# HDMI.net
KiCad netlist of a schematic drawn in Altium Designer
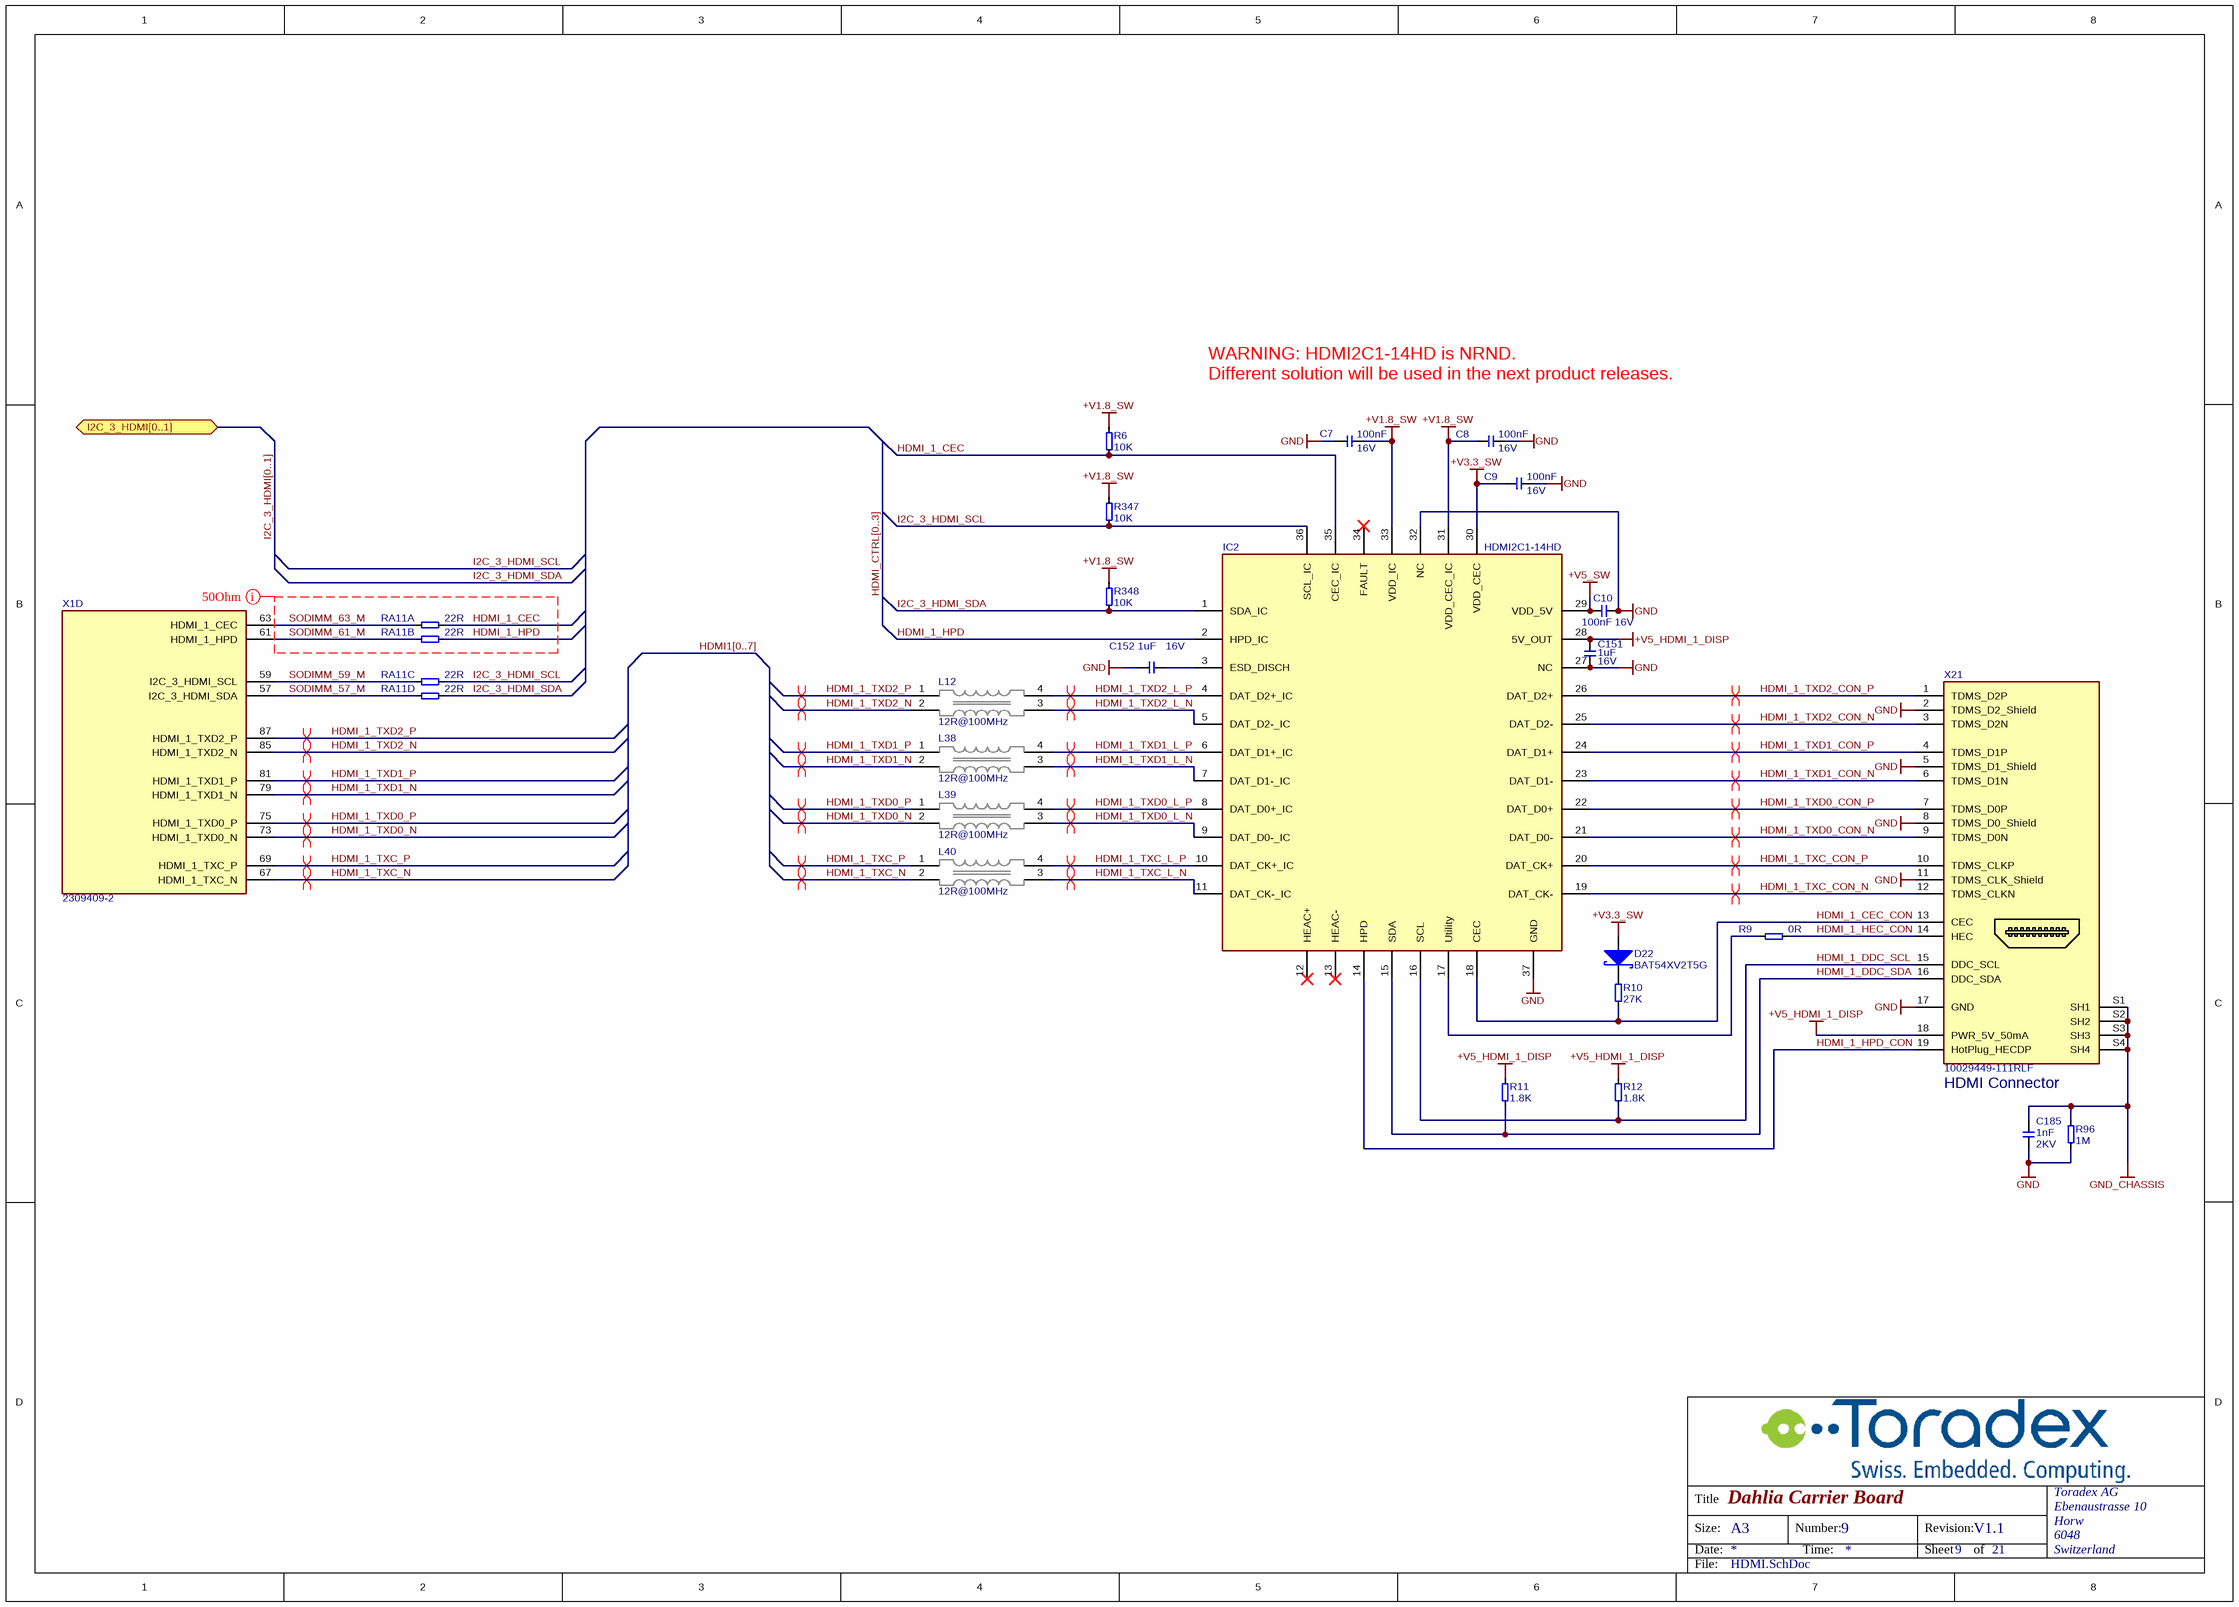
[diagram p0: HDMI.SchDoc]

(export (version "E")
  (design (tool "Eeschema 10.0.6"))
  (components
    (comp (ref "C7")
      (value "100nF")
      (footprint "CAPC1005X60N")
      (description "Capacitor Ceramic X7R 100nF 16V 10% 0402")
      (fields (field (name "TOLERANCE") "10%") (field (name "RATING") "16V"))
      (libsource (lib "Dahlia Carrier Board") (part "C-X7R-100nF-16V-10%-0402"))
    )
    (comp (ref "C8")
      (value "100nF")
      (footprint "CAPC1005X60N")
      (description "Capacitor Ceramic X7R 100nF 16V 10% 0402")
      (fields (field (name "TOLERANCE") "10%") (field (name "RATING") "16V"))
      (libsource (lib "Dahlia Carrier Board") (part "C-X7R-100nF-16V-10%-0402"))
    )
    (comp (ref "C9")
      (value "100nF")
      (footprint "CAPC1005X60N")
      (description "Capacitor Ceramic X7R 100nF 16V 10% 0402")
      (fields (field (name "TOLERANCE") "10%") (field (name "RATING") "16V"))
      (libsource (lib "Dahlia Carrier Board") (part "C-X7R-100nF-16V-10%-0402"))
    )
    (comp (ref "C10")
      (value "100nF")
      (footprint "CAPC1005X60N")
      (description "Capacitor Ceramic X7R 100nF 16V 10% 0402")
      (fields (field (name "TOLERANCE") "10%") (field (name "RATING") "16V"))
      (libsource (lib "Dahlia Carrier Board") (part "C-X7R-100nF-16V-10%-0402"))
    )
    (comp (ref "C151")
      (value "1uF")
      (footprint "CAPC1005X60N")
      (description "Capacitor Ceramic X5R 1uF 16V 20% 0402")
      (fields (field (name "TOLERANCE") "20%") (field (name "RATING") "16V"))
      (libsource (lib "Dahlia Carrier Board") (part "C-X5R-1uF-16V-20%-0402"))
    )
    (comp (ref "C152")
      (value "1uF")
      (footprint "CAPC1005X60N")
      (description "Capacitor Ceramic X5R 1uF 16V 20% 0402")
      (fields (field (name "TOLERANCE") "20%") (field (name "RATING") "16V"))
      (libsource (lib "Dahlia Carrier Board") (part "C-X5R-1uF-16V-20%-0402"))
    )
    (comp (ref "C185")
      (value "1nF")
      (footprint "T_CAPC1206X180N")
      (description "Capacitor Ceramic X7R 1nF 2KV 10% 1206")
      (fields (field (name "TOLERANCE") "10%") (field (name "RATING") "2KV"))
      (libsource (lib "Dahlia Carrier Board") (part "C-X7R-1nF-2KV-10%-1206"))
    )
    (comp (ref "D22")
      (value "BAT54XV2T5G")
      (footprint "SOD-523")
      (description "Schottky Barrier Rectifier")
      (fields (field (name "MANUFACTURER PART NO.") "BAT54XV2T5G"))
      (libsource (lib "Dahlia Carrier Board") (part "D-BAT54-SOD523"))
    )
    (comp (ref "IC2")
      (value "HDMI2C1-14HD")
      (footprint "QFN50P350X650X95_HS-37N")
      (description "ESD protection and signal conditioning for HDMI™ 2.0 source interface")
      (fields (field (name "MANUFACTURER PART NO.") "HDMI2C1-14HD"))
      (libsource (lib "Dahlia Carrier Board") (part "IC-ST-HDMI2C1-14HD"))
    )
    (comp (ref "L12")
      (value "12R@100MHz")
      (footprint "T_Panasonic_EXC14CH120U")
      (description "Common Mode Choke High Speed 12R 100mA")
      (fields (field (name "TOLERANCE") "25%") (field (name "MANUFACTURER PART NO.") "EXC14CH120U"))
      (libsource (lib "Dahlia Carrier Board") (part "L-Panasonic-EXC14CH120U-12R@100MHz-1000mA-25%"))
    )
    (comp (ref "L38")
      (value "12R@100MHz")
      (footprint "T_Panasonic_EXC14CH120U")
      (description "Common Mode Choke High Speed 12R 100mA")
      (fields (field (name "TOLERANCE") "25%") (field (name "MANUFACTURER PART NO.") "EXC14CH120U"))
      (libsource (lib "Dahlia Carrier Board") (part "L-Panasonic-EXC14CH120U-12R@100MHz-1000mA-25%"))
    )
    (comp (ref "L39")
      (value "12R@100MHz")
      (footprint "T_Panasonic_EXC14CH120U")
      (description "Common Mode Choke High Speed 12R 100mA")
      (fields (field (name "TOLERANCE") "25%") (field (name "MANUFACTURER PART NO.") "EXC14CH120U"))
      (libsource (lib "Dahlia Carrier Board") (part "L-Panasonic-EXC14CH120U-12R@100MHz-1000mA-25%"))
    )
    (comp (ref "L40")
      (value "12R@100MHz")
      (footprint "T_Panasonic_EXC14CH120U")
      (description "Common Mode Choke High Speed 12R 100mA")
      (fields (field (name "TOLERANCE") "25%") (field (name "MANUFACTURER PART NO.") "EXC14CH120U"))
      (libsource (lib "Dahlia Carrier Board") (part "L-Panasonic-EXC14CH120U-12R@100MHz-1000mA-25%"))
    )
    (comp (ref "R6")
      (value "10K")
      (footprint "RESC1005X40N")
      (description "Resistor 10 Kohm 63mW 5% 0402")
      (fields (field (name "TOLERANCE") "5%"))
      (libsource (lib "Dahlia Carrier Board") (part "R-10K-63mW-5%-0402"))
    )
    (comp (ref "R9")
      (value "0R")
      (footprint "T_RESC0603X30N")
      (description "Resistor 0 ohm 63mW 1% 0603")
      (fields (field (name "TOLERANCE") "1%"))
      (libsource (lib "Dahlia Carrier Board") (part "R-0R-63mW-1%-0603"))
    )
    (comp (ref "R10")
      (value "27K")
      (footprint "RESC1005X40N")
      (description "Resistor 27 Kohm 63mW 5% 0402")
      (fields (field (name "TOLERANCE") "5%"))
      (libsource (lib "Dahlia Carrier Board") (part "R-27K-63mW-5%-0402"))
    )
    (comp (ref "R11")
      (value "1.8K")
      (footprint "RESC1005X40N")
      (description "Resistor 1.8 Kohm 63mW 5% 0402")
      (fields (field (name "TOLERANCE") "5%"))
      (libsource (lib "Dahlia Carrier Board") (part "R-1.8K-63mW-5%-0402"))
    )
    (comp (ref "R12")
      (value "1.8K")
      (footprint "RESC1005X40N")
      (description "Resistor 1.8 Kohm 63mW 5% 0402")
      (fields (field (name "TOLERANCE") "5%"))
      (libsource (lib "Dahlia Carrier Board") (part "R-1.8K-63mW-5%-0402"))
    )
    (comp (ref "R96")
      (value "1M")
      (footprint "RESC3216X75N")
      (description "Resistor 1 Mohm 250mW 5% 1206")
      (fields (field (name "TOLERANCE") "5%"))
      (libsource (lib "Dahlia Carrier Board") (part "R-1M-250mW-5%-1206"))
    )
    (comp (ref "R347")
      (value "10K")
      (footprint "RESC1005X40N")
      (description "Resistor 10 Kohm 63mW 5% 0402")
      (fields (field (name "TOLERANCE") "5%"))
      (libsource (lib "Dahlia Carrier Board") (part "R-10K-63mW-5%-0402"))
    )
    (comp (ref "R348")
      (value "10K")
      (footprint "RESC1005X40N")
      (description "Resistor 10 Kohm 63mW 5% 0402")
      (fields (field (name "TOLERANCE") "5%"))
      (libsource (lib "Dahlia Carrier Board") (part "R-10K-63mW-5%-0402"))
    )
    (comp (ref "RA11")
      (value "22R")
      (footprint "T_Resistor_Array_X4")
      (description "Resistor Array 22 R 63mW 5% 1206")
      (fields (field (name "TOLERANCE") "5%"))
      (libsource (lib "Dahlia Carrier Board") (part "RA-22R-63mW-5%-1206-div"))
    )
    (comp (ref "X1")
      (value "2309409-2")
      (footprint "CON-TE-2309409-2-SOLDERABLE-STANDOFFS")
      (description "DDR4 SODIMM Socket, 260 pins, 5.2mm(H), 0.5mm Pitch")
      (libsource (lib "Dahlia Carrier Board") (part "CON-TE-2309409-2"))
    )
    (comp (ref "X21")
      (value "10029449-111RLF")
      (footprint "T_FCI_10029449-111RLF")
      (description "HDMI Connector Right Angle Vertical THT")
      (fields (field (name "MANUFACTURER PART NO.") "10029449-111RLF"))
      (libsource (lib "Dahlia Carrier Board") (part "CON-FCI-10029449-111RLF"))
    )
  )
  (nets
    (net (code "15") (name "+V1.8_SW") (class "Default")
      (node (ref "C7") (pin "2") (pinfunction "2_2") (pintype "passive"))
      (node (ref "C8") (pin "1") (pinfunction "1_1") (pintype "passive"))
      (node (ref "IC2") (pin "31") (pinfunction "VDD_CEC_IC_31") (pintype "passive"))
      (node (ref "IC2") (pin "33") (pinfunction "VDD_IC_33") (pintype "power_in"))
      (node (ref "R347") (pin "1") (pinfunction "1_1") (pintype "passive"))
      (node (ref "R348") (pin "1") (pinfunction "1_1") (pintype "passive"))
      (node (ref "R6") (pin "2") (pinfunction "2_2") (pintype "passive"))
    )
    (net (code "16") (name "+V3.3_SW") (class "Default")
      (node (ref "C9") (pin "2") (pinfunction "2_2") (pintype "passive"))
      (node (ref "D22") (pin "A") (pinfunction "A_A") (pintype "passive"))
      (node (ref "IC2") (pin "30") (pinfunction "VDD_CEC_30") (pintype "passive"))
    )
    (net (code "17") (name "+V5_HDMI_1_DISP") (class "Default")
      (node (ref "C151") (pin "2") (pinfunction "2_2") (pintype "passive"))
      (node (ref "IC2") (pin "28") (pinfunction "5V_OUT_28") (pintype "power_in"))
      (node (ref "R11") (pin "2") (pinfunction "2_2") (pintype "passive"))
      (node (ref "R12") (pin "2") (pinfunction "2_2") (pintype "passive"))
      (node (ref "X21") (pin "18") (pinfunction "PWR_5V_50mA_18") (pintype "passive"))
    )
    (net (code "18") (name "+V5_SW") (class "Default")
      (node (ref "C10") (pin "2") (pinfunction "2_2") (pintype "passive"))
      (node (ref "IC2") (pin "29") (pinfunction "VDD_5V_29") (pintype "power_in"))
    )
    (net (code "20") (name "/HDMI_1_CEC") (class "Default")
      (node (ref "IC2") (pin "35") (pinfunction "CEC_IC_35") (pintype "passive"))
      (node (ref "R6") (pin "1") (pinfunction "1_1") (pintype "passive"))
      (node (ref "RA11") (pin "5") (pinfunction "5_5") (pintype "passive"))
    )
    (net (code "21") (name "/HDMI_1_CEC_CON") (class "Default")
      (node (ref "IC2") (pin "18") (pinfunction "CEC_18") (pintype "passive"))
      (node (ref "R10") (pin "1") (pinfunction "1_1") (pintype "passive"))
      (node (ref "X21") (pin "13") (pinfunction "CEC_13") (pintype "passive"))
    )
    (net (code "22") (name "/HDMI_1_DDC_SCL") (class "Default")
      (node (ref "IC2") (pin "16") (pinfunction "SCL_16") (pintype "passive"))
      (node (ref "R12") (pin "1") (pinfunction "1_1") (pintype "passive"))
      (node (ref "X21") (pin "15") (pinfunction "DDC_SCL_15") (pintype "passive"))
    )
    (net (code "23") (name "/HDMI_1_DDC_SDA") (class "Default")
      (node (ref "IC2") (pin "15") (pinfunction "SDA_15") (pintype "passive"))
      (node (ref "R11") (pin "1") (pinfunction "1_1") (pintype "passive"))
      (node (ref "X21") (pin "16") (pinfunction "DDC_SDA_16") (pintype "passive"))
    )
    (net (code "24") (name "/HDMI_1_HEC_CON") (class "Default")
      (node (ref "R9") (pin "2") (pinfunction "2_2") (pintype "passive"))
      (node (ref "X21") (pin "14") (pinfunction "HEC_14") (pintype "passive"))
    )
    (net (code "25") (name "/HDMI_1_HPD") (class "Default")
      (node (ref "IC2") (pin "2") (pinfunction "HPD_IC_2") (pintype "passive"))
      (node (ref "RA11") (pin "6") (pinfunction "6_6") (pintype "passive"))
    )
    (net (code "26") (name "/HDMI_1_HPD_CON") (class "Default")
      (node (ref "IC2") (pin "14") (pinfunction "HPD_14") (pintype "passive"))
      (node (ref "X21") (pin "19") (pinfunction "HotPlug_HECDP_19") (pintype "passive"))
    )
    (net (code "27") (name "/HDMI_1_TXC_CON_N") (class "Default")
      (node (ref "IC2") (pin "19") (pinfunction "DAT_CK-_19") (pintype "passive"))
      (node (ref "X21") (pin "12") (pinfunction "TDMS_CLKN_12") (pintype "passive"))
    )
    (net (code "28") (name "/HDMI_1_TXC_CON_P") (class "Default")
      (node (ref "IC2") (pin "20") (pinfunction "DAT_CK+_20") (pintype "passive"))
      (node (ref "X21") (pin "10") (pinfunction "TDMS_CLKP_10") (pintype "passive"))
    )
    (net (code "29") (name "/HDMI_1_TXC_L_N") (class "Default")
      (node (ref "IC2") (pin "11") (pinfunction "DAT_CK-_IC_11") (pintype "passive"))
      (node (ref "L40") (pin "3") (pinfunction "3_3") (pintype "passive"))
    )
    (net (code "30") (name "/HDMI_1_TXC_L_P") (class "Default")
      (node (ref "IC2") (pin "10") (pinfunction "DAT_CK+_IC_10") (pintype "passive"))
      (node (ref "L40") (pin "4") (pinfunction "4_4") (pintype "passive"))
    )
    (net (code "31") (name "/HDMI_1_TXC_N") (class "Default")
      (node (ref "L40") (pin "2") (pinfunction "2_2") (pintype "passive"))
      (node (ref "X1") (pin "67") (pinfunction "HDMI_1_TXC_N_67") (pintype "passive"))
    )
    (net (code "32") (name "/HDMI_1_TXC_P") (class "Default")
      (node (ref "L40") (pin "1") (pinfunction "1_1") (pintype "passive"))
      (node (ref "X1") (pin "69") (pinfunction "HDMI_1_TXC_P_69") (pintype "passive"))
    )
    (net (code "33") (name "/HDMI_1_TXD0_CON_N") (class "Default")
      (node (ref "IC2") (pin "21") (pinfunction "DAT_D0-_21") (pintype "passive"))
      (node (ref "X21") (pin "9") (pinfunction "TDMS_D0N_9") (pintype "passive"))
    )
    (net (code "34") (name "/HDMI_1_TXD0_CON_P") (class "Default")
      (node (ref "IC2") (pin "22") (pinfunction "DAT_D0+_22") (pintype "passive"))
      (node (ref "X21") (pin "7") (pinfunction "TDMS_D0P_7") (pintype "passive"))
    )
    (net (code "35") (name "/HDMI_1_TXD0_L_N") (class "Default")
      (node (ref "IC2") (pin "9") (pinfunction "DAT_D0-_IC_9") (pintype "passive"))
      (node (ref "L39") (pin "3") (pinfunction "3_3") (pintype "passive"))
    )
    (net (code "36") (name "/HDMI_1_TXD0_L_P") (class "Default")
      (node (ref "IC2") (pin "8") (pinfunction "DAT_D0+_IC_8") (pintype "passive"))
      (node (ref "L39") (pin "4") (pinfunction "4_4") (pintype "passive"))
    )
    (net (code "37") (name "/HDMI_1_TXD0_N") (class "Default")
      (node (ref "L39") (pin "2") (pinfunction "2_2") (pintype "passive"))
      (node (ref "X1") (pin "73") (pinfunction "HDMI_1_TXD0_N_73") (pintype "passive"))
    )
    (net (code "38") (name "/HDMI_1_TXD0_P") (class "Default")
      (node (ref "L39") (pin "1") (pinfunction "1_1") (pintype "passive"))
      (node (ref "X1") (pin "75") (pinfunction "HDMI_1_TXD0_P_75") (pintype "passive"))
    )
    (net (code "39") (name "/HDMI_1_TXD1_CON_N") (class "Default")
      (node (ref "IC2") (pin "23") (pinfunction "DAT_D1-_23") (pintype "passive"))
      (node (ref "X21") (pin "6") (pinfunction "TDMS_D1N_6") (pintype "passive"))
    )
    (net (code "40") (name "/HDMI_1_TXD1_CON_P") (class "Default")
      (node (ref "IC2") (pin "24") (pinfunction "DAT_D1+_24") (pintype "passive"))
      (node (ref "X21") (pin "4") (pinfunction "TDMS_D1P_4") (pintype "passive"))
    )
    (net (code "41") (name "/HDMI_1_TXD1_L_N") (class "Default")
      (node (ref "IC2") (pin "7") (pinfunction "DAT_D1-_IC_7") (pintype "passive"))
      (node (ref "L38") (pin "3") (pinfunction "3_3") (pintype "passive"))
    )
    (net (code "42") (name "/HDMI_1_TXD1_L_P") (class "Default")
      (node (ref "IC2") (pin "6") (pinfunction "DAT_D1+_IC_6") (pintype "passive"))
      (node (ref "L38") (pin "4") (pinfunction "4_4") (pintype "passive"))
    )
    (net (code "43") (name "/HDMI_1_TXD1_N") (class "Default")
      (node (ref "L38") (pin "2") (pinfunction "2_2") (pintype "passive"))
      (node (ref "X1") (pin "79") (pinfunction "HDMI_1_TXD1_N_79") (pintype "passive"))
    )
    (net (code "44") (name "/HDMI_1_TXD1_P") (class "Default")
      (node (ref "L38") (pin "1") (pinfunction "1_1") (pintype "passive"))
      (node (ref "X1") (pin "81") (pinfunction "HDMI_1_TXD1_P_81") (pintype "passive"))
    )
    (net (code "45") (name "/HDMI_1_TXD2_CON_N") (class "Default")
      (node (ref "IC2") (pin "25") (pinfunction "DAT_D2-_25") (pintype "passive"))
      (node (ref "X21") (pin "3") (pinfunction "TDMS_D2N_3") (pintype "passive"))
    )
    (net (code "46") (name "/HDMI_1_TXD2_CON_P") (class "Default")
      (node (ref "IC2") (pin "26") (pinfunction "DAT_D2+_26") (pintype "passive"))
      (node (ref "X21") (pin "1") (pinfunction "TDMS_D2P_1") (pintype "passive"))
    )
    (net (code "47") (name "/HDMI_1_TXD2_L_N") (class "Default")
      (node (ref "IC2") (pin "5") (pinfunction "DAT_D2-_IC_5") (pintype "passive"))
      (node (ref "L12") (pin "3") (pinfunction "3_3") (pintype "passive"))
    )
    (net (code "48") (name "/HDMI_1_TXD2_L_P") (class "Default")
      (node (ref "IC2") (pin "4") (pinfunction "DAT_D2+_IC_4") (pintype "passive"))
      (node (ref "L12") (pin "4") (pinfunction "4_4") (pintype "passive"))
    )
    (net (code "49") (name "/HDMI_1_TXD2_N") (class "Default")
      (node (ref "L12") (pin "2") (pinfunction "2_2") (pintype "passive"))
      (node (ref "X1") (pin "85") (pinfunction "HDMI_1_TXD2_N_85") (pintype "passive"))
    )
    (net (code "50") (name "/HDMI_1_TXD2_P") (class "Default")
      (node (ref "L12") (pin "1") (pinfunction "1_1") (pintype "passive"))
      (node (ref "X1") (pin "87") (pinfunction "HDMI_1_TXD2_P_87") (pintype "passive"))
    )
    (net (code "53") (name "/I2C_3_HDMI_SCL") (class "Default")
      (node (ref "IC2") (pin "36") (pinfunction "SCL_IC_36") (pintype "passive"))
      (node (ref "R347") (pin "2") (pinfunction "2_2") (pintype "passive"))
      (node (ref "RA11") (pin "7") (pinfunction "7_7") (pintype "passive"))
    )
    (net (code "54") (name "/I2C_3_HDMI_SDA") (class "Default")
      (node (ref "IC2") (pin "1") (pinfunction "SDA_IC_1") (pintype "passive"))
      (node (ref "R348") (pin "2") (pinfunction "2_2") (pintype "passive"))
      (node (ref "RA11") (pin "8") (pinfunction "8_8") (pintype "passive"))
    )
    (net (code "55") (name "/SODIMM_57_M") (class "Default")
      (node (ref "RA11") (pin "4") (pinfunction "4_4") (pintype "passive"))
      (node (ref "X1") (pin "57") (pinfunction "I2C_3_HDMI_SDA_57") (pintype "passive"))
    )
    (net (code "56") (name "/SODIMM_59_M") (class "Default")
      (node (ref "RA11") (pin "3") (pinfunction "3_3") (pintype "passive"))
      (node (ref "X1") (pin "59") (pinfunction "I2C_3_HDMI_SCL_59") (pintype "passive"))
    )
    (net (code "57") (name "/SODIMM_61_M") (class "Default")
      (node (ref "RA11") (pin "2") (pinfunction "2_2") (pintype "passive"))
      (node (ref "X1") (pin "61") (pinfunction "HDMI_1_HPD_61") (pintype "passive"))
    )
    (net (code "58") (name "/SODIMM_63_M") (class "Default")
      (node (ref "RA11") (pin "1") (pinfunction "1_1") (pintype "passive"))
      (node (ref "X1") (pin "63") (pinfunction "HDMI_1_CEC_63") (pintype "passive"))
    )
    (net (code "59") (name "GND") (class "Default")
      (node (ref "C10") (pin "1") (pinfunction "1_1") (pintype "passive"))
      (node (ref "C151") (pin "1") (pinfunction "1_1") (pintype "passive"))
      (node (ref "C152") (pin "2") (pinfunction "2_2") (pintype "passive"))
      (node (ref "C185") (pin "1") (pinfunction "1_1") (pintype "passive"))
      (node (ref "C7") (pin "1") (pinfunction "1_1") (pintype "passive"))
      (node (ref "C8") (pin "2") (pinfunction "2_2") (pintype "passive"))
      (node (ref "C9") (pin "1") (pinfunction "1_1") (pintype "passive"))
      (node (ref "IC2") (pin "27") (pinfunction "NC_27") (pintype "passive"))
      (node (ref "IC2") (pin "32") (pinfunction "NC_32") (pintype "passive"))
      (node (ref "IC2") (pin "37") (pinfunction "GND_37") (pintype "power_in"))
      (node (ref "R96") (pin "1") (pinfunction "1_1") (pintype "passive"))
      (node (ref "X21") (pin "11") (pinfunction "TDMS_CLK_Shield_11") (pintype "passive"))
      (node (ref "X21") (pin "17") (pinfunction "GND_17") (pintype "passive"))
      (node (ref "X21") (pin "2") (pinfunction "TDMS_D2_Shield_2") (pintype "passive"))
      (node (ref "X21") (pin "5") (pinfunction "TDMS_D1_Shield_5") (pintype "passive"))
      (node (ref "X21") (pin "8") (pinfunction "TDMS_D0_Shield_8") (pintype "passive"))
    )
    (net (code "60") (name "GND_CHASSIS") (class "Default")
      (node (ref "C185") (pin "2") (pinfunction "2_2") (pintype "passive"))
      (node (ref "R96") (pin "2") (pinfunction "2_2") (pintype "passive"))
      (node (ref "X21") (pin "S1") (pinfunction "SH1_S1") (pintype "passive"))
      (node (ref "X21") (pin "S2") (pinfunction "SH2_S2") (pintype "passive"))
      (node (ref "X21") (pin "S3") (pinfunction "SH3_S3") (pintype "passive"))
      (node (ref "X21") (pin "S4") (pinfunction "SH4_S4") (pintype "passive"))
    )
    (net (code "61") (name "Net-(D22-PadC)") (class "Default")
      (node (ref "D22") (pin "C") (pinfunction "C_C") (pintype "passive"))
      (node (ref "R10") (pin "2") (pinfunction "2_2") (pintype "passive"))
    )
    (net (code "62") (name "Net-(IC2-ESD_DISCH)") (class "Default")
      (node (ref "C152") (pin "1") (pinfunction "1_1") (pintype "passive"))
      (node (ref "IC2") (pin "3") (pinfunction "ESD_DISCH_3") (pintype "passive"))
    )
    (net (code "63") (name "Net-(IC2-Utility)") (class "Default")
      (node (ref "IC2") (pin "17") (pinfunction "Utility_17") (pintype "passive"))
      (node (ref "R9") (pin "1") (pinfunction "1_1") (pintype "passive"))
    )
    (net (code "64") (name "unconnected-(IC2-FAULT-Pad34)") (class "Default")
      (node (ref "IC2") (pin "34") (pinfunction "FAULT_34") (pintype "passive+no_connect"))
    )
    (net (code "65") (name "unconnected-(IC2-HEAC+-Pad12)") (class "Default")
      (node (ref "IC2") (pin "12") (pinfunction "HEAC+_12") (pintype "passive+no_connect"))
    )
    (net (code "66") (name "unconnected-(IC2-HEAC--Pad13)") (class "Default")
      (node (ref "IC2") (pin "13") (pinfunction "HEAC-_13") (pintype "passive+no_connect"))
    )
  )
)
